# clock2.net
KiCad netlist of a schematic drawn in EAGLE
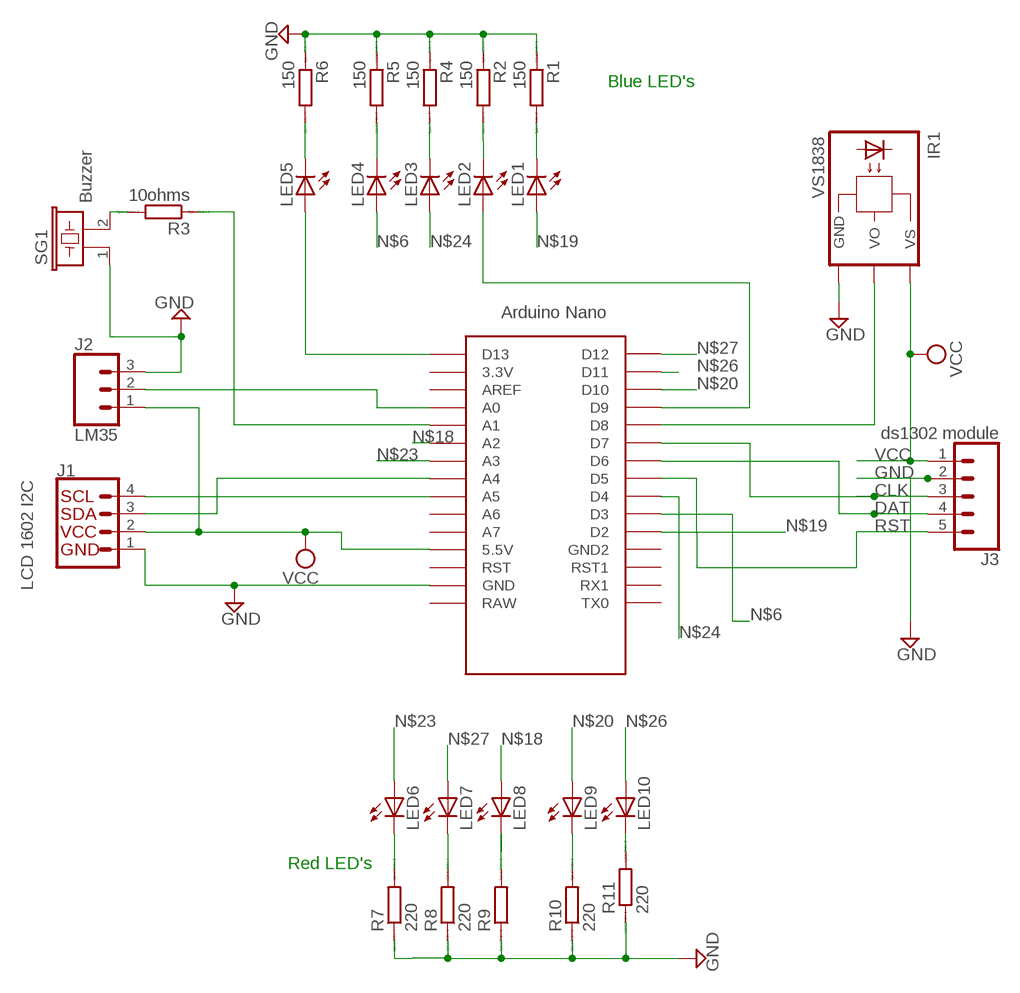
[diagram p0: schematic, sheet 1]

(export (version "E")
  (design (tool "Eeschema 10.0.6"))
  (components
    (comp (ref "IR1")
      (value "VS1838")
      (footprint "eagle-import:TSOP17_TB1")
      (libsource (lib "eagle-import") (part "TSOP17TB130"))
    )
    (comp (ref "J1")
      (value "LCD 1602 I2C")
      (footprint "eagle-import:1X04")
      (libsource (lib "eagle-import") (part "I2C_STANDARD"))
    )
    (comp (ref "J2")
      (value "LM35")
      (footprint "eagle-import:1X03")
      (libsource (lib "eagle-import") (part "CONN_03"))
    )
    (comp (ref "J3")
      (value "ds1302 module")
      (footprint "eagle-import:1X05")
      (libsource (lib "eagle-import") (part "CONN_05"))
    )
    (comp (ref "LED1")
      (value "LED5MM")
      (footprint "eagle-import:LED5MM")
      (libsource (lib "eagle-import") (part "LED5MM"))
    )
    (comp (ref "LED2")
      (value "LED5MM")
      (footprint "eagle-import:LED5MM")
      (libsource (lib "eagle-import") (part "LED5MM"))
    )
    (comp (ref "LED3")
      (value "LED5MM")
      (footprint "eagle-import:LED5MM")
      (libsource (lib "eagle-import") (part "LED5MM"))
    )
    (comp (ref "LED4")
      (value "LED5MM")
      (footprint "eagle-import:LED5MM")
      (libsource (lib "eagle-import") (part "LED5MM"))
    )
    (comp (ref "LED5")
      (value "LED5MM")
      (footprint "eagle-import:LED5MM")
      (libsource (lib "eagle-import") (part "LED5MM"))
    )
    (comp (ref "LED6")
      (value "LED5MM")
      (footprint "eagle-import:LED5MM")
      (libsource (lib "eagle-import") (part "LED5MM"))
    )
    (comp (ref "LED7")
      (value "LED5MM")
      (footprint "eagle-import:LED5MM")
      (libsource (lib "eagle-import") (part "LED5MM"))
    )
    (comp (ref "LED8")
      (value "LED5MM")
      (footprint "eagle-import:LED5MM")
      (libsource (lib "eagle-import") (part "LED5MM"))
    )
    (comp (ref "LED9")
      (value "LED5MM")
      (footprint "eagle-import:LED5MM")
      (libsource (lib "eagle-import") (part "LED5MM"))
    )
    (comp (ref "LED10")
      (value "LED5MM")
      (footprint "eagle-import:LED5MM")
      (libsource (lib "eagle-import") (part "LED5MM"))
    )
    (comp (ref "R1")
      (value "150")
      (footprint "eagle-import:0204_7")
      (libsource (lib "eagle-import") (part "R0204/7"))
    )
    (comp (ref "R2")
      (value "150")
      (footprint "eagle-import:0204_7")
      (libsource (lib "eagle-import") (part "R0204/7"))
    )
    (comp (ref "R3")
      (value "10ohms")
      (footprint "eagle-import:0204_7")
      (libsource (lib "eagle-import") (part "R0204/7"))
    )
    (comp (ref "R4")
      (value "150")
      (footprint "eagle-import:0204_7")
      (libsource (lib "eagle-import") (part "R0204/7"))
    )
    (comp (ref "R5")
      (value "150")
      (footprint "eagle-import:0204_7")
      (libsource (lib "eagle-import") (part "R0204/7"))
    )
    (comp (ref "R6")
      (value "150")
      (footprint "eagle-import:0204_7")
      (libsource (lib "eagle-import") (part "R0204/7"))
    )
    (comp (ref "R7")
      (value "220")
      (footprint "eagle-import:0204_7")
      (libsource (lib "eagle-import") (part "R0204/7"))
    )
    (comp (ref "R8")
      (value "220")
      (footprint "eagle-import:0204_7")
      (libsource (lib "eagle-import") (part "R0204/7"))
    )
    (comp (ref "R9")
      (value "R0204/7")
      (footprint "eagle-import:0204_7")
      (libsource (lib "eagle-import") (part "R0204/7"))
    )
    (comp (ref "R10")
      (value "220")
      (footprint "eagle-import:0204_7")
      (libsource (lib "eagle-import") (part "R0204/7"))
    )
    (comp (ref "R11")
      (value "220")
      (footprint "eagle-import:0204_7")
      (libsource (lib "eagle-import") (part "R0204/7"))
    )
    (comp (ref "SG1")
      (value "Buzzer")
      (footprint "eagle-import:B_C17L")
      (libsource (lib "eagle-import") (part "B/C17L"))
    )
    (comp (ref "U$1")
      (value "NANO")
      (footprint "eagle-import:NANO")
      (libsource (lib "eagle-import") (part "NANO"))
    )
  )
  (nets
    (net (code "1") (name "/CLK") (class "Default")
      (node (ref "J3") (pin "3") (pinfunction "3_3") (pintype "passive"))
      (node (ref "U$1") (pin "D7") (pinfunction "D7_D7") (pintype "bidirectional"))
    )
    (net (code "2") (name "/DAT") (class "Default")
      (node (ref "J3") (pin "4") (pinfunction "4_4") (pintype "passive"))
      (node (ref "U$1") (pin "D6") (pinfunction "D6_D6") (pintype "bidirectional"))
    )
    (net (code "3") (name "/N$6") (class "Default")
      (node (ref "LED4") (pin "A") (pinfunction "A_A") (pintype "passive"))
      (node (ref "U$1") (pin "D3") (pinfunction "D3_D3") (pintype "bidirectional"))
    )
    (net (code "4") (name "/N$18") (class "Default")
      (node (ref "LED8") (pin "A") (pinfunction "A_A") (pintype "passive"))
    )
    (net (code "5") (name "/N$19") (class "Default")
      (node (ref "U$1") (pin "D2") (pinfunction "D2_D2") (pintype "bidirectional"))
    )
    (net (code "6") (name "/N$20") (class "Default")
      (node (ref "LED9") (pin "A") (pinfunction "A_A") (pintype "passive"))
    )
    (net (code "7") (name "/N$23") (class "Default")
      (node (ref "LED6") (pin "A") (pinfunction "A_A") (pintype "passive"))
    )
    (net (code "8") (name "/N$24") (class "Default")
      (node (ref "LED3") (pin "A") (pinfunction "A_A") (pintype "passive"))
      (node (ref "U$1") (pin "D4") (pinfunction "D4_D4") (pintype "bidirectional"))
    )
    (net (code "9") (name "/N$26") (class "Default")
      (node (ref "LED10") (pin "A") (pinfunction "A_A") (pintype "passive"))
    )
    (net (code "10") (name "/N$27") (class "Default")
      (node (ref "LED7") (pin "A") (pinfunction "A_A") (pintype "passive"))
      (node (ref "U$1") (pin "D12") (pinfunction "D12_D12") (pintype "bidirectional"))
    )
    (net (code "11") (name "/RST") (class "Default")
      (node (ref "J3") (pin "5") (pinfunction "5_5") (pintype "passive"))
      (node (ref "U$1") (pin "D5") (pinfunction "D5_D5") (pintype "bidirectional"))
    )
    (net (code "12") (name "GND") (class "Default")
      (node (ref "IR1") (pin "GND") (pinfunction "GND_GND") (pintype "power_in"))
      (node (ref "J1") (pin "1") (pinfunction "1_1") (pintype "power_in"))
      (node (ref "J2") (pin "3") (pinfunction "3_3") (pintype "passive"))
      (node (ref "J3") (pin "2") (pinfunction "2_2") (pintype "passive"))
      (node (ref "R1") (pin "1") (pinfunction "1_1") (pintype "passive"))
      (node (ref "R10") (pin "1") (pinfunction "1_1") (pintype "passive"))
      (node (ref "R11") (pin "1") (pinfunction "1_1") (pintype "passive"))
      (node (ref "R2") (pin "1") (pinfunction "1_1") (pintype "passive"))
      (node (ref "R4") (pin "1") (pinfunction "1_1") (pintype "passive"))
      (node (ref "R5") (pin "1") (pinfunction "1_1") (pintype "passive"))
      (node (ref "R6") (pin "1") (pinfunction "1_1") (pintype "passive"))
      (node (ref "R7") (pin "1") (pinfunction "1_1") (pintype "passive"))
      (node (ref "R8") (pin "1") (pinfunction "1_1") (pintype "passive"))
      (node (ref "R9") (pin "1") (pinfunction "1_1") (pintype "passive"))
      (node (ref "SG1") (pin "1") (pinfunction "1_1") (pintype "passive"))
      (node (ref "U$1") (pin "GND") (pinfunction "GND_GND") (pintype "bidirectional"))
    )
    (net (code "13") (name "Net-(IR1-PadVO)") (class "Default")
      (node (ref "IR1") (pin "VO") (pinfunction "VO_VO") (pintype "open_collector"))
      (node (ref "U$1") (pin "D8") (pinfunction "D8_D8") (pintype "bidirectional"))
    )
    (net (code "14") (name "Net-(J1-Pad3)") (class "Default")
      (node (ref "J1") (pin "3") (pinfunction "3_3") (pintype "passive"))
      (node (ref "U$1") (pin "A4") (pinfunction "A4_A4") (pintype "bidirectional"))
    )
    (net (code "15") (name "Net-(J1-Pad4)") (class "Default")
      (node (ref "J1") (pin "4") (pinfunction "4_4") (pintype "passive"))
      (node (ref "U$1") (pin "A5") (pinfunction "A5_A5") (pintype "bidirectional"))
    )
    (net (code "16") (name "Net-(J2-Pad2)") (class "Default")
      (node (ref "J2") (pin "2") (pinfunction "2_2") (pintype "passive"))
      (node (ref "U$1") (pin "A0") (pinfunction "A0_A0") (pintype "bidirectional"))
    )
    (net (code "17") (name "Net-(LED1-C)") (class "Default")
      (node (ref "LED1") (pin "K") (pinfunction "C_K") (pintype "passive"))
      (node (ref "R1") (pin "2") (pinfunction "2_2") (pintype "passive"))
    )
    (net (code "18") (name "Net-(LED2-C)") (class "Default")
      (node (ref "LED2") (pin "K") (pinfunction "C_K") (pintype "passive"))
      (node (ref "R2") (pin "2") (pinfunction "2_2") (pintype "passive"))
    )
    (net (code "19") (name "Net-(LED2-PadA)") (class "Default")
      (node (ref "LED2") (pin "A") (pinfunction "A_A") (pintype "passive"))
      (node (ref "U$1") (pin "D9") (pinfunction "D9_D9") (pintype "bidirectional"))
    )
    (net (code "20") (name "Net-(LED3-C)") (class "Default")
      (node (ref "LED3") (pin "K") (pinfunction "C_K") (pintype "passive"))
      (node (ref "R4") (pin "2") (pinfunction "2_2") (pintype "passive"))
    )
    (net (code "21") (name "Net-(LED4-C)") (class "Default")
      (node (ref "LED4") (pin "K") (pinfunction "C_K") (pintype "passive"))
      (node (ref "R5") (pin "2") (pinfunction "2_2") (pintype "passive"))
    )
    (net (code "22") (name "Net-(LED5-C)") (class "Default")
      (node (ref "LED5") (pin "K") (pinfunction "C_K") (pintype "passive"))
      (node (ref "R6") (pin "2") (pinfunction "2_2") (pintype "passive"))
    )
    (net (code "23") (name "Net-(LED5-PadA)") (class "Default")
      (node (ref "LED5") (pin "A") (pinfunction "A_A") (pintype "passive"))
      (node (ref "U$1") (pin "D13") (pinfunction "D13_D13") (pintype "bidirectional"))
    )
    (net (code "24") (name "Net-(LED6-C)") (class "Default")
      (node (ref "LED6") (pin "K") (pinfunction "C_K") (pintype "passive"))
      (node (ref "R7") (pin "2") (pinfunction "2_2") (pintype "passive"))
    )
    (net (code "25") (name "Net-(LED7-C)") (class "Default")
      (node (ref "LED7") (pin "K") (pinfunction "C_K") (pintype "passive"))
      (node (ref "R8") (pin "2") (pinfunction "2_2") (pintype "passive"))
    )
    (net (code "26") (name "Net-(LED8-C)") (class "Default")
      (node (ref "LED8") (pin "K") (pinfunction "C_K") (pintype "passive"))
      (node (ref "R9") (pin "2") (pinfunction "2_2") (pintype "passive"))
    )
    (net (code "27") (name "Net-(LED9-C)") (class "Default")
      (node (ref "LED9") (pin "K") (pinfunction "C_K") (pintype "passive"))
      (node (ref "R10") (pin "2") (pinfunction "2_2") (pintype "passive"))
    )
    (net (code "28") (name "Net-(LED10-C)") (class "Default")
      (node (ref "LED10") (pin "K") (pinfunction "C_K") (pintype "passive"))
      (node (ref "R11") (pin "2") (pinfunction "2_2") (pintype "passive"))
    )
    (net (code "29") (name "Net-(R3-Pad1)") (class "Default")
      (node (ref "R3") (pin "1") (pinfunction "1_1") (pintype "passive"))
      (node (ref "U$1") (pin "A1") (pinfunction "A1_A1") (pintype "bidirectional"))
    )
    (net (code "30") (name "Net-(R3-Pad2)") (class "Default")
      (node (ref "R3") (pin "2") (pinfunction "2_2") (pintype "passive"))
      (node (ref "SG1") (pin "2") (pinfunction "2_2") (pintype "passive"))
    )
    (net (code "31") (name "VCC") (class "Default")
      (node (ref "IR1") (pin "VS") (pinfunction "VS_VS") (pintype "power_in"))
      (node (ref "J1") (pin "2") (pinfunction "2_2") (pintype "power_in"))
      (node (ref "J2") (pin "1") (pinfunction "1_1") (pintype "passive"))
      (node (ref "J3") (pin "1") (pinfunction "1_1") (pintype "passive"))
      (node (ref "U$1") (pin "5V") (pinfunction "5.5V_5V") (pintype "bidirectional"))
    )
    (net (code "32") (name "unconnected-(LED1-PadA)") (class "Default")
      (node (ref "LED1") (pin "A") (pinfunction "A_A") (pintype "passive"))
    )
    (net (code "33") (name "unconnected-(U$1-GND2-PadGND1)") (class "Default")
      (node (ref "U$1") (pin "GND1") (pinfunction "GND2_GND1") (pintype "bidirectional"))
    )
    (net (code "34") (name "unconnected-(U$1-Pad3.3V)") (class "Default")
      (node (ref "U$1") (pin "3.3V") (pinfunction "3.3V_3.3V") (pintype "bidirectional"))
    )
    (net (code "35") (name "unconnected-(U$1-PadA2)") (class "Default")
      (node (ref "U$1") (pin "A2") (pinfunction "A2_A2") (pintype "bidirectional"))
    )
    (net (code "36") (name "unconnected-(U$1-PadA3)") (class "Default")
      (node (ref "U$1") (pin "A3") (pinfunction "A3_A3") (pintype "bidirectional"))
    )
    (net (code "37") (name "unconnected-(U$1-PadA6)") (class "Default")
      (node (ref "U$1") (pin "A6") (pinfunction "A6_A6") (pintype "bidirectional"))
    )
    (net (code "38") (name "unconnected-(U$1-PadA7)") (class "Default")
      (node (ref "U$1") (pin "A7") (pinfunction "A7_A7") (pintype "bidirectional"))
    )
    (net (code "39") (name "unconnected-(U$1-PadAREF)") (class "Default")
      (node (ref "U$1") (pin "AREF") (pinfunction "AREF_AREF") (pintype "bidirectional"))
    )
    (net (code "40") (name "unconnected-(U$1-PadD10)") (class "Default")
      (node (ref "U$1") (pin "D10") (pinfunction "D10_D10") (pintype "bidirectional"))
    )
    (net (code "41") (name "unconnected-(U$1-PadD11)") (class "Default")
      (node (ref "U$1") (pin "D11") (pinfunction "D11_D11") (pintype "bidirectional"))
    )
    (net (code "42") (name "unconnected-(U$1-PadICSP1)") (class "Default")
      (node (ref "U$1") (pin "ICSP1") (pinfunction "ICSP1_ICSP1") (pintype "bidirectional"))
    )
    (net (code "43") (name "unconnected-(U$1-PadICSP2)") (class "Default")
      (node (ref "U$1") (pin "ICSP2") (pinfunction "ICSP2_ICSP2") (pintype "bidirectional"))
    )
    (net (code "44") (name "unconnected-(U$1-PadICSP3)") (class "Default")
      (node (ref "U$1") (pin "ICSP3") (pinfunction "ICSP3_ICSP3") (pintype "bidirectional"))
    )
    (net (code "45") (name "unconnected-(U$1-PadICSP4)") (class "Default")
      (node (ref "U$1") (pin "ICSP4") (pinfunction "ICSP4_ICSP4") (pintype "bidirectional"))
    )
    (net (code "46") (name "unconnected-(U$1-PadICSP5)") (class "Default")
      (node (ref "U$1") (pin "ICSP5") (pinfunction "ICSP5_ICSP5") (pintype "bidirectional"))
    )
    (net (code "47") (name "unconnected-(U$1-PadICSP6)") (class "Default")
      (node (ref "U$1") (pin "ICSP6") (pinfunction "ICSP6_ICSP6") (pintype "bidirectional"))
    )
    (net (code "48") (name "unconnected-(U$1-PadRAW)") (class "Default")
      (node (ref "U$1") (pin "RAW") (pinfunction "RAW_RAW") (pintype "bidirectional"))
    )
    (net (code "49") (name "unconnected-(U$1-PadRST)") (class "Default")
      (node (ref "U$1") (pin "RST") (pinfunction "RST_RST") (pintype "bidirectional"))
    )
    (net (code "50") (name "unconnected-(U$1-PadRST1)") (class "Default")
      (node (ref "U$1") (pin "RST1") (pinfunction "RST1_RST1") (pintype "bidirectional"))
    )
    (net (code "51") (name "unconnected-(U$1-PadRX1)") (class "Default")
      (node (ref "U$1") (pin "RX1") (pinfunction "RX1_RX1") (pintype "bidirectional"))
    )
    (net (code "52") (name "unconnected-(U$1-PadTX0)") (class "Default")
      (node (ref "U$1") (pin "TX0") (pinfunction "TX0_TX0") (pintype "bidirectional"))
    )
  )
)
